# Schema.net
KiCad netlist of a schematic drawn in EAGLE
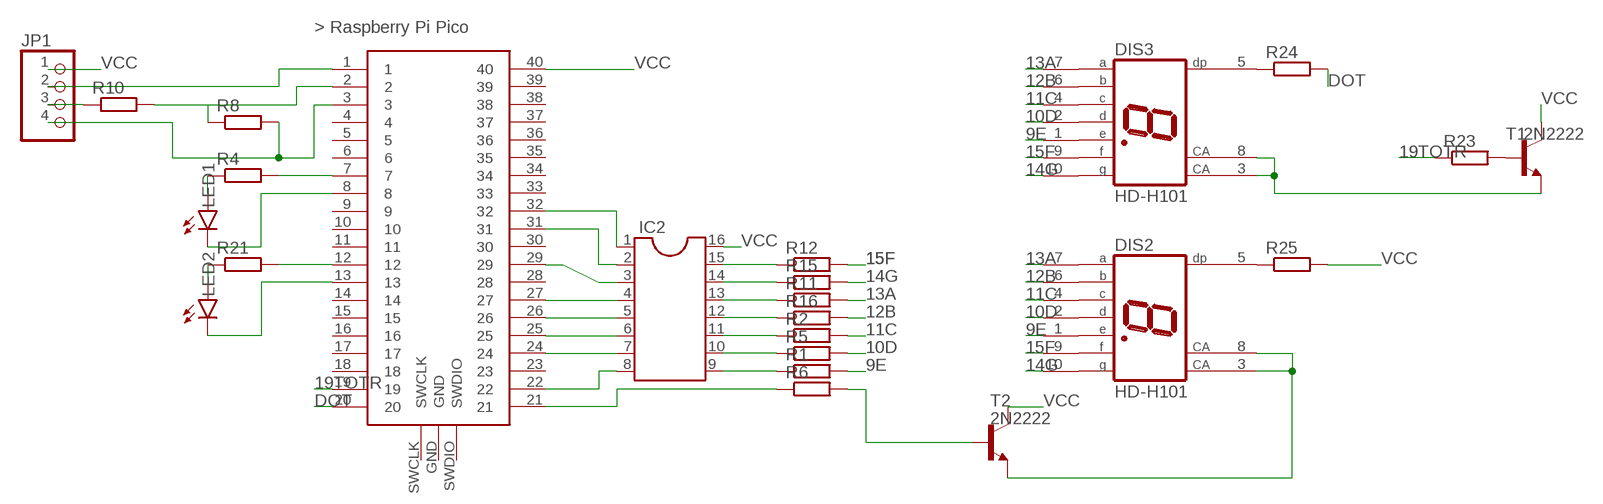
[diagram p0: schematic, sheet 1]

(export (version "E")
  (design (tool "Eeschema 10.0.6"))
  (components
    (comp (ref "DIS2")
      (value "HD-H101")
      (footprint "eagle-import:HDSP-M")
      (libsource (lib "eagle-import") (part "HD-H101"))
    )
    (comp (ref "DIS3")
      (value "HD-H101")
      (footprint "eagle-import:HDSP-M")
      (libsource (lib "eagle-import") (part "HD-H101"))
    )
    (comp (ref "IC2")
      (value "DIL16")
      (footprint "eagle-import:DIL16")
      (libsource (lib "eagle-import") (part "DIL16"))
    )
    (comp (ref "JP1")
      (value "PINHD-1X4")
      (footprint "eagle-import:1X04")
      (libsource (lib "eagle-import") (part "PINHD-1X4"))
    )
    (comp (ref "LED1")
      (value "LED5MM")
      (footprint "eagle-import:LED5MM")
      (libsource (lib "eagle-import") (part "LED5MM"))
    )
    (comp (ref "LED2")
      (value "LED5MM")
      (footprint "eagle-import:LED5MM")
      (libsource (lib "eagle-import") (part "LED5MM"))
    )
    (comp (ref "R1")
      (value "R-EU_0207/10")
      (footprint "eagle-import:0207_10")
      (libsource (lib "eagle-import") (part "R-EU_0207/10"))
    )
    (comp (ref "R2")
      (value "R-EU_0207/10")
      (footprint "eagle-import:0207_10")
      (libsource (lib "eagle-import") (part "R-EU_0207/10"))
    )
    (comp (ref "R4")
      (value "R-EU_0207/10")
      (footprint "eagle-import:0207_10")
      (libsource (lib "eagle-import") (part "R-EU_0207/10"))
    )
    (comp (ref "R5")
      (value "R-EU_0207/10")
      (footprint "eagle-import:0207_10")
      (libsource (lib "eagle-import") (part "R-EU_0207/10"))
    )
    (comp (ref "R6")
      (value "R-EU_0207/10")
      (footprint "eagle-import:0207_10")
      (libsource (lib "eagle-import") (part "R-EU_0207/10"))
    )
    (comp (ref "R8")
      (value "R-EU_0207/10")
      (footprint "eagle-import:0207_10")
      (libsource (lib "eagle-import") (part "R-EU_0207/10"))
    )
    (comp (ref "R10")
      (value "R-EU_0207/10")
      (footprint "eagle-import:0207_10")
      (libsource (lib "eagle-import") (part "R-EU_0207/10"))
    )
    (comp (ref "R11")
      (value "R-EU_0207/10")
      (footprint "eagle-import:0207_10")
      (libsource (lib "eagle-import") (part "R-EU_0207/10"))
    )
    (comp (ref "R12")
      (value "R-EU_0207/10")
      (footprint "eagle-import:0207_10")
      (libsource (lib "eagle-import") (part "R-EU_0207/10"))
    )
    (comp (ref "R15")
      (value "R-EU_0207/10")
      (footprint "eagle-import:0207_10")
      (libsource (lib "eagle-import") (part "R-EU_0207/10"))
    )
    (comp (ref "R16")
      (value "R-EU_0207/10")
      (footprint "eagle-import:0207_10")
      (libsource (lib "eagle-import") (part "R-EU_0207/10"))
    )
    (comp (ref "R21")
      (value "R-EU_0207/10")
      (footprint "eagle-import:0207_10")
      (libsource (lib "eagle-import") (part "R-EU_0207/10"))
    )
    (comp (ref "R23")
      (value "R-EU_0207/10")
      (footprint "eagle-import:0207_10")
      (libsource (lib "eagle-import") (part "R-EU_0207/10"))
    )
    (comp (ref "R24")
      (value "R-EU_0207/10")
      (footprint "eagle-import:0207_10")
      (libsource (lib "eagle-import") (part "R-EU_0207/10"))
    )
    (comp (ref "R25")
      (value "R-EU_0207/10")
      (footprint "eagle-import:0207_10")
      (libsource (lib "eagle-import") (part "R-EU_0207/10"))
    )
    (comp (ref "T1")
      (value "2N2222")
      (footprint "eagle-import:TO18")
      (libsource (lib "eagle-import") (part "2N2222"))
    )
    (comp (ref "T2")
      (value "2N2222")
      (footprint "eagle-import:TO18")
      (libsource (lib "eagle-import") (part "2N2222"))
    )
    (comp (ref "U$1")
      (value "RASPBERRY-PI-PICO_TH")
      (footprint "eagle-import:FT_RASPBERRY-PI-PICO_TH")
      (libsource (lib "eagle-import") (part "RASPBERRY-PI-PICO_TH"))
    )
  )
  (nets
    (net (code "1") (name "/9E") (class "Default")
      (node (ref "DIS2") (pin "1") (pinfunction "E_1") (pintype "passive"))
      (node (ref "DIS3") (pin "1") (pinfunction "E_1") (pintype "passive"))
      (node (ref "R1") (pin "2") (pinfunction "2_2") (pintype "passive"))
    )
    (net (code "2") (name "/10D") (class "Default")
      (node (ref "DIS2") (pin "2") (pinfunction "D_2") (pintype "passive"))
      (node (ref "DIS3") (pin "2") (pinfunction "D_2") (pintype "passive"))
      (node (ref "R5") (pin "2") (pinfunction "2_2") (pintype "passive"))
    )
    (net (code "3") (name "/11C") (class "Default")
      (node (ref "DIS2") (pin "4") (pinfunction "C_4") (pintype "passive"))
      (node (ref "DIS3") (pin "4") (pinfunction "C_4") (pintype "passive"))
      (node (ref "R2") (pin "2") (pinfunction "2_2") (pintype "passive"))
    )
    (net (code "4") (name "/12B") (class "Default")
      (node (ref "DIS2") (pin "6") (pinfunction "B_6") (pintype "passive"))
      (node (ref "DIS3") (pin "6") (pinfunction "B_6") (pintype "passive"))
      (node (ref "R16") (pin "2") (pinfunction "2_2") (pintype "passive"))
    )
    (net (code "5") (name "/13A") (class "Default")
      (node (ref "DIS2") (pin "7") (pinfunction "A_7") (pintype "passive"))
      (node (ref "DIS3") (pin "7") (pinfunction "A_7") (pintype "passive"))
      (node (ref "R11") (pin "2") (pinfunction "2_2") (pintype "passive"))
    )
    (net (code "6") (name "/14G") (class "Default")
      (node (ref "DIS2") (pin "10") (pinfunction "G_10") (pintype "passive"))
      (node (ref "DIS3") (pin "10") (pinfunction "G_10") (pintype "passive"))
      (node (ref "R15") (pin "2") (pinfunction "2_2") (pintype "passive"))
    )
    (net (code "7") (name "/15F") (class "Default")
      (node (ref "DIS2") (pin "9") (pinfunction "F_9") (pintype "passive"))
      (node (ref "DIS3") (pin "9") (pinfunction "F_9") (pintype "passive"))
      (node (ref "R12") (pin "2") (pinfunction "2_2") (pintype "passive"))
    )
    (net (code "8") (name "/19TOTR") (class "Default")
      (node (ref "R23") (pin "1") (pinfunction "1_1") (pintype "passive"))
      (node (ref "U$1") (pin "19") (pinfunction "19_19") (pintype "bidirectional"))
    )
    (net (code "9") (name "/DOT") (class "Default")
      (node (ref "R24") (pin "2") (pinfunction "2_2") (pintype "passive"))
      (node (ref "U$1") (pin "20") (pinfunction "20_20") (pintype "bidirectional"))
    )
    (net (code "10") (name "/VCC") (class "Default")
      (node (ref "IC2") (pin "16") (pinfunction "16_16") (pintype "passive"))
      (node (ref "JP1") (pin "1") (pinfunction "1_1") (pintype "passive"))
      (node (ref "R25") (pin "2") (pinfunction "2_2") (pintype "passive"))
      (node (ref "T1") (pin "3") (pinfunction "C_3") (pintype "passive"))
      (node (ref "T2") (pin "3") (pinfunction "C_3") (pintype "passive"))
      (node (ref "U$1") (pin "40") (pinfunction "40_40") (pintype "bidirectional"))
    )
    (net (code "11") (name "Net-(DIS2-DP)") (class "Default")
      (node (ref "DIS2") (pin "5") (pinfunction "DP_5") (pintype "passive"))
      (node (ref "R25") (pin "1") (pinfunction "1_1") (pintype "passive"))
    )
    (net (code "12") (name "Net-(DIS3-DP)") (class "Default")
      (node (ref "DIS3") (pin "5") (pinfunction "DP_5") (pintype "passive"))
      (node (ref "R24") (pin "1") (pinfunction "1_1") (pintype "passive"))
    )
    (net (code "13") (name "Net-(IC2-Pad1)") (class "Default")
      (node (ref "IC2") (pin "1") (pinfunction "1_1") (pintype "passive"))
      (node (ref "U$1") (pin "32") (pinfunction "32_32") (pintype "bidirectional"))
    )
    (net (code "14") (name "Net-(IC2-Pad2)") (class "Default")
      (node (ref "IC2") (pin "2") (pinfunction "2_2") (pintype "passive"))
      (node (ref "U$1") (pin "31") (pinfunction "31_31") (pintype "bidirectional"))
    )
    (net (code "15") (name "Net-(IC2-Pad3)") (class "Default")
      (node (ref "IC2") (pin "3") (pinfunction "3_3") (pintype "passive"))
      (node (ref "U$1") (pin "29") (pinfunction "29_29") (pintype "bidirectional"))
    )
    (net (code "16") (name "Net-(IC2-Pad4)") (class "Default")
      (node (ref "IC2") (pin "4") (pinfunction "4_4") (pintype "passive"))
      (node (ref "U$1") (pin "27") (pinfunction "27_27") (pintype "bidirectional"))
    )
    (net (code "17") (name "Net-(IC2-Pad5)") (class "Default")
      (node (ref "IC2") (pin "5") (pinfunction "5_5") (pintype "passive"))
      (node (ref "U$1") (pin "26") (pinfunction "26_26") (pintype "bidirectional"))
    )
    (net (code "18") (name "Net-(IC2-Pad6)") (class "Default")
      (node (ref "IC2") (pin "6") (pinfunction "6_6") (pintype "passive"))
      (node (ref "U$1") (pin "25") (pinfunction "25_25") (pintype "bidirectional"))
    )
    (net (code "19") (name "Net-(IC2-Pad7)") (class "Default")
      (node (ref "IC2") (pin "7") (pinfunction "7_7") (pintype "passive"))
      (node (ref "U$1") (pin "24") (pinfunction "24_24") (pintype "bidirectional"))
    )
    (net (code "20") (name "Net-(IC2-Pad8)") (class "Default")
      (node (ref "IC2") (pin "8") (pinfunction "8_8") (pintype "passive"))
      (node (ref "U$1") (pin "22") (pinfunction "22_22") (pintype "bidirectional"))
    )
    (net (code "21") (name "Net-(IC2-Pad9)") (class "Default")
      (node (ref "IC2") (pin "9") (pinfunction "9_9") (pintype "passive"))
      (node (ref "R1") (pin "1") (pinfunction "1_1") (pintype "passive"))
    )
    (net (code "22") (name "Net-(IC2-Pad10)") (class "Default")
      (node (ref "IC2") (pin "10") (pinfunction "10_10") (pintype "passive"))
      (node (ref "R5") (pin "1") (pinfunction "1_1") (pintype "passive"))
    )
    (net (code "23") (name "Net-(IC2-Pad11)") (class "Default")
      (node (ref "IC2") (pin "11") (pinfunction "11_11") (pintype "passive"))
      (node (ref "R2") (pin "1") (pinfunction "1_1") (pintype "passive"))
    )
    (net (code "24") (name "Net-(IC2-Pad12)") (class "Default")
      (node (ref "IC2") (pin "12") (pinfunction "12_12") (pintype "passive"))
      (node (ref "R16") (pin "1") (pinfunction "1_1") (pintype "passive"))
    )
    (net (code "25") (name "Net-(IC2-Pad13)") (class "Default")
      (node (ref "IC2") (pin "13") (pinfunction "13_13") (pintype "passive"))
      (node (ref "R11") (pin "1") (pinfunction "1_1") (pintype "passive"))
    )
    (net (code "26") (name "Net-(IC2-Pad14)") (class "Default")
      (node (ref "IC2") (pin "14") (pinfunction "14_14") (pintype "passive"))
      (node (ref "R15") (pin "1") (pinfunction "1_1") (pintype "passive"))
    )
    (net (code "27") (name "Net-(IC2-Pad15)") (class "Default")
      (node (ref "IC2") (pin "15") (pinfunction "15_15") (pintype "passive"))
      (node (ref "R12") (pin "1") (pinfunction "1_1") (pintype "passive"))
    )
    (net (code "28") (name "Net-(JP1-Pad2)") (class "Default")
      (node (ref "JP1") (pin "2") (pinfunction "2_2") (pintype "passive"))
      (node (ref "U$1") (pin "1") (pinfunction "1_1") (pintype "bidirectional"))
    )
    (net (code "29") (name "Net-(JP1-Pad3)") (class "Default")
      (node (ref "JP1") (pin "3") (pinfunction "3_3") (pintype "passive"))
      (node (ref "R10") (pin "1") (pinfunction "1_1") (pintype "passive"))
    )
    (net (code "30") (name "Net-(JP1-Pad4)") (class "Default")
      (node (ref "JP1") (pin "4") (pinfunction "4_4") (pintype "passive"))
      (node (ref "R8") (pin "2") (pinfunction "2_2") (pintype "passive"))
      (node (ref "U$1") (pin "3") (pinfunction "3_3") (pintype "bidirectional"))
    )
    (net (code "31") (name "Net-(LED1-C)") (class "Default")
      (node (ref "LED1") (pin "K") (pinfunction "C_K") (pintype "passive"))
      (node (ref "U$1") (pin "8") (pinfunction "8_8") (pintype "bidirectional"))
    )
    (net (code "32") (name "Net-(LED1-PadA)") (class "Default")
      (node (ref "LED1") (pin "A") (pinfunction "A_A") (pintype "passive"))
      (node (ref "R4") (pin "1") (pinfunction "1_1") (pintype "passive"))
    )
    (net (code "33") (name "Net-(LED2-C)") (class "Default")
      (node (ref "LED2") (pin "K") (pinfunction "C_K") (pintype "passive"))
      (node (ref "U$1") (pin "13") (pinfunction "13_13") (pintype "bidirectional"))
    )
    (net (code "34") (name "Net-(LED2-PadA)") (class "Default")
      (node (ref "LED2") (pin "A") (pinfunction "A_A") (pintype "passive"))
      (node (ref "R21") (pin "1") (pinfunction "1_1") (pintype "passive"))
    )
    (net (code "35") (name "Net-(R4-Pad2)") (class "Default")
      (node (ref "R4") (pin "2") (pinfunction "2_2") (pintype "passive"))
      (node (ref "U$1") (pin "7") (pinfunction "7_7") (pintype "bidirectional"))
    )
    (net (code "36") (name "Net-(R6-Pad1)") (class "Default")
      (node (ref "R6") (pin "1") (pinfunction "1_1") (pintype "passive"))
      (node (ref "U$1") (pin "21") (pinfunction "21_21") (pintype "bidirectional"))
    )
    (net (code "37") (name "Net-(R10-Pad2)") (class "Default")
      (node (ref "R10") (pin "2") (pinfunction "2_2") (pintype "passive"))
      (node (ref "R8") (pin "1") (pinfunction "1_1") (pintype "passive"))
      (node (ref "U$1") (pin "2") (pinfunction "2_2") (pintype "bidirectional"))
    )
    (net (code "38") (name "Net-(R21-Pad2)") (class "Default")
      (node (ref "R21") (pin "2") (pinfunction "2_2") (pintype "passive"))
      (node (ref "U$1") (pin "12") (pinfunction "12_12") (pintype "bidirectional"))
    )
    (net (code "39") (name "Net-(T1-B)") (class "Default")
      (node (ref "R23") (pin "2") (pinfunction "2_2") (pintype "passive"))
      (node (ref "T1") (pin "2") (pinfunction "B_2") (pintype "passive"))
    )
    (net (code "40") (name "Net-(T1-E)") (class "Default")
      (node (ref "DIS3") (pin "3") (pinfunction "CA_3") (pintype "passive"))
      (node (ref "DIS3") (pin "8") (pinfunction "CA_8") (pintype "passive"))
      (node (ref "T1") (pin "1") (pinfunction "E_1") (pintype "passive"))
    )
    (net (code "41") (name "Net-(T2-B)") (class "Default")
      (node (ref "R6") (pin "2") (pinfunction "2_2") (pintype "passive"))
      (node (ref "T2") (pin "2") (pinfunction "B_2") (pintype "passive"))
    )
    (net (code "42") (name "Net-(T2-E)") (class "Default")
      (node (ref "DIS2") (pin "3") (pinfunction "CA_3") (pintype "passive"))
      (node (ref "DIS2") (pin "8") (pinfunction "CA_8") (pintype "passive"))
      (node (ref "T2") (pin "1") (pinfunction "E_1") (pintype "passive"))
    )
    (net (code "43") (name "unconnected-(U$1-Pad4)") (class "Default")
      (node (ref "U$1") (pin "4") (pinfunction "4_4") (pintype "bidirectional"))
    )
    (net (code "44") (name "unconnected-(U$1-Pad5)") (class "Default")
      (node (ref "U$1") (pin "5") (pinfunction "5_5") (pintype "bidirectional"))
    )
    (net (code "45") (name "unconnected-(U$1-Pad6)") (class "Default")
      (node (ref "U$1") (pin "6") (pinfunction "6_6") (pintype "bidirectional"))
    )
    (net (code "46") (name "unconnected-(U$1-Pad9)") (class "Default")
      (node (ref "U$1") (pin "9") (pinfunction "9_9") (pintype "bidirectional"))
    )
    (net (code "47") (name "unconnected-(U$1-Pad10)") (class "Default")
      (node (ref "U$1") (pin "10") (pinfunction "10_10") (pintype "bidirectional"))
    )
    (net (code "48") (name "unconnected-(U$1-Pad11)") (class "Default")
      (node (ref "U$1") (pin "11") (pinfunction "11_11") (pintype "bidirectional"))
    )
    (net (code "49") (name "unconnected-(U$1-Pad14)") (class "Default")
      (node (ref "U$1") (pin "14") (pinfunction "14_14") (pintype "bidirectional"))
    )
    (net (code "50") (name "unconnected-(U$1-Pad15)") (class "Default")
      (node (ref "U$1") (pin "15") (pinfunction "15_15") (pintype "bidirectional"))
    )
    (net (code "51") (name "unconnected-(U$1-Pad16)") (class "Default")
      (node (ref "U$1") (pin "16") (pinfunction "16_16") (pintype "bidirectional"))
    )
    (net (code "52") (name "unconnected-(U$1-Pad17)") (class "Default")
      (node (ref "U$1") (pin "17") (pinfunction "17_17") (pintype "bidirectional"))
    )
    (net (code "53") (name "unconnected-(U$1-Pad18)") (class "Default")
      (node (ref "U$1") (pin "18") (pinfunction "18_18") (pintype "bidirectional"))
    )
    (net (code "54") (name "unconnected-(U$1-Pad23)") (class "Default")
      (node (ref "U$1") (pin "23") (pinfunction "23_23") (pintype "bidirectional"))
    )
    (net (code "55") (name "unconnected-(U$1-Pad28)") (class "Default")
      (node (ref "U$1") (pin "28") (pinfunction "28_28") (pintype "bidirectional"))
    )
    (net (code "56") (name "unconnected-(U$1-Pad30)") (class "Default")
      (node (ref "U$1") (pin "30") (pinfunction "30_30") (pintype "bidirectional"))
    )
    (net (code "57") (name "unconnected-(U$1-Pad33)") (class "Default")
      (node (ref "U$1") (pin "33") (pinfunction "33_33") (pintype "bidirectional"))
    )
    (net (code "58") (name "unconnected-(U$1-Pad34)") (class "Default")
      (node (ref "U$1") (pin "34") (pinfunction "34_34") (pintype "bidirectional"))
    )
    (net (code "59") (name "unconnected-(U$1-Pad35)") (class "Default")
      (node (ref "U$1") (pin "35") (pinfunction "35_35") (pintype "bidirectional"))
    )
    (net (code "60") (name "unconnected-(U$1-Pad36)") (class "Default")
      (node (ref "U$1") (pin "36") (pinfunction "36_36") (pintype "bidirectional"))
    )
    (net (code "61") (name "unconnected-(U$1-Pad37)") (class "Default")
      (node (ref "U$1") (pin "37") (pinfunction "37_37") (pintype "bidirectional"))
    )
    (net (code "62") (name "unconnected-(U$1-Pad38)") (class "Default")
      (node (ref "U$1") (pin "38") (pinfunction "38_38") (pintype "bidirectional"))
    )
    (net (code "63") (name "unconnected-(U$1-Pad39)") (class "Default")
      (node (ref "U$1") (pin "39") (pinfunction "39_39") (pintype "bidirectional"))
    )
    (net (code "64") (name "unconnected-(U$1-PadGND)") (class "Default")
      (node (ref "U$1") (pin "GND") (pinfunction "GND_GND") (pintype "bidirectional"))
    )
    (net (code "65") (name "unconnected-(U$1-PadSWCLK)") (class "Default")
      (node (ref "U$1") (pin "SWCLK") (pinfunction "SWCLK_SWCLK") (pintype "bidirectional"))
    )
    (net (code "66") (name "unconnected-(U$1-PadSWDIO)") (class "Default")
      (node (ref "U$1") (pin "SWDIO") (pinfunction "SWDIO_SWDIO") (pintype "bidirectional"))
    )
  )
)
